# circuit_roboag.net
KiCad netlist of a schematic drawn in EAGLE
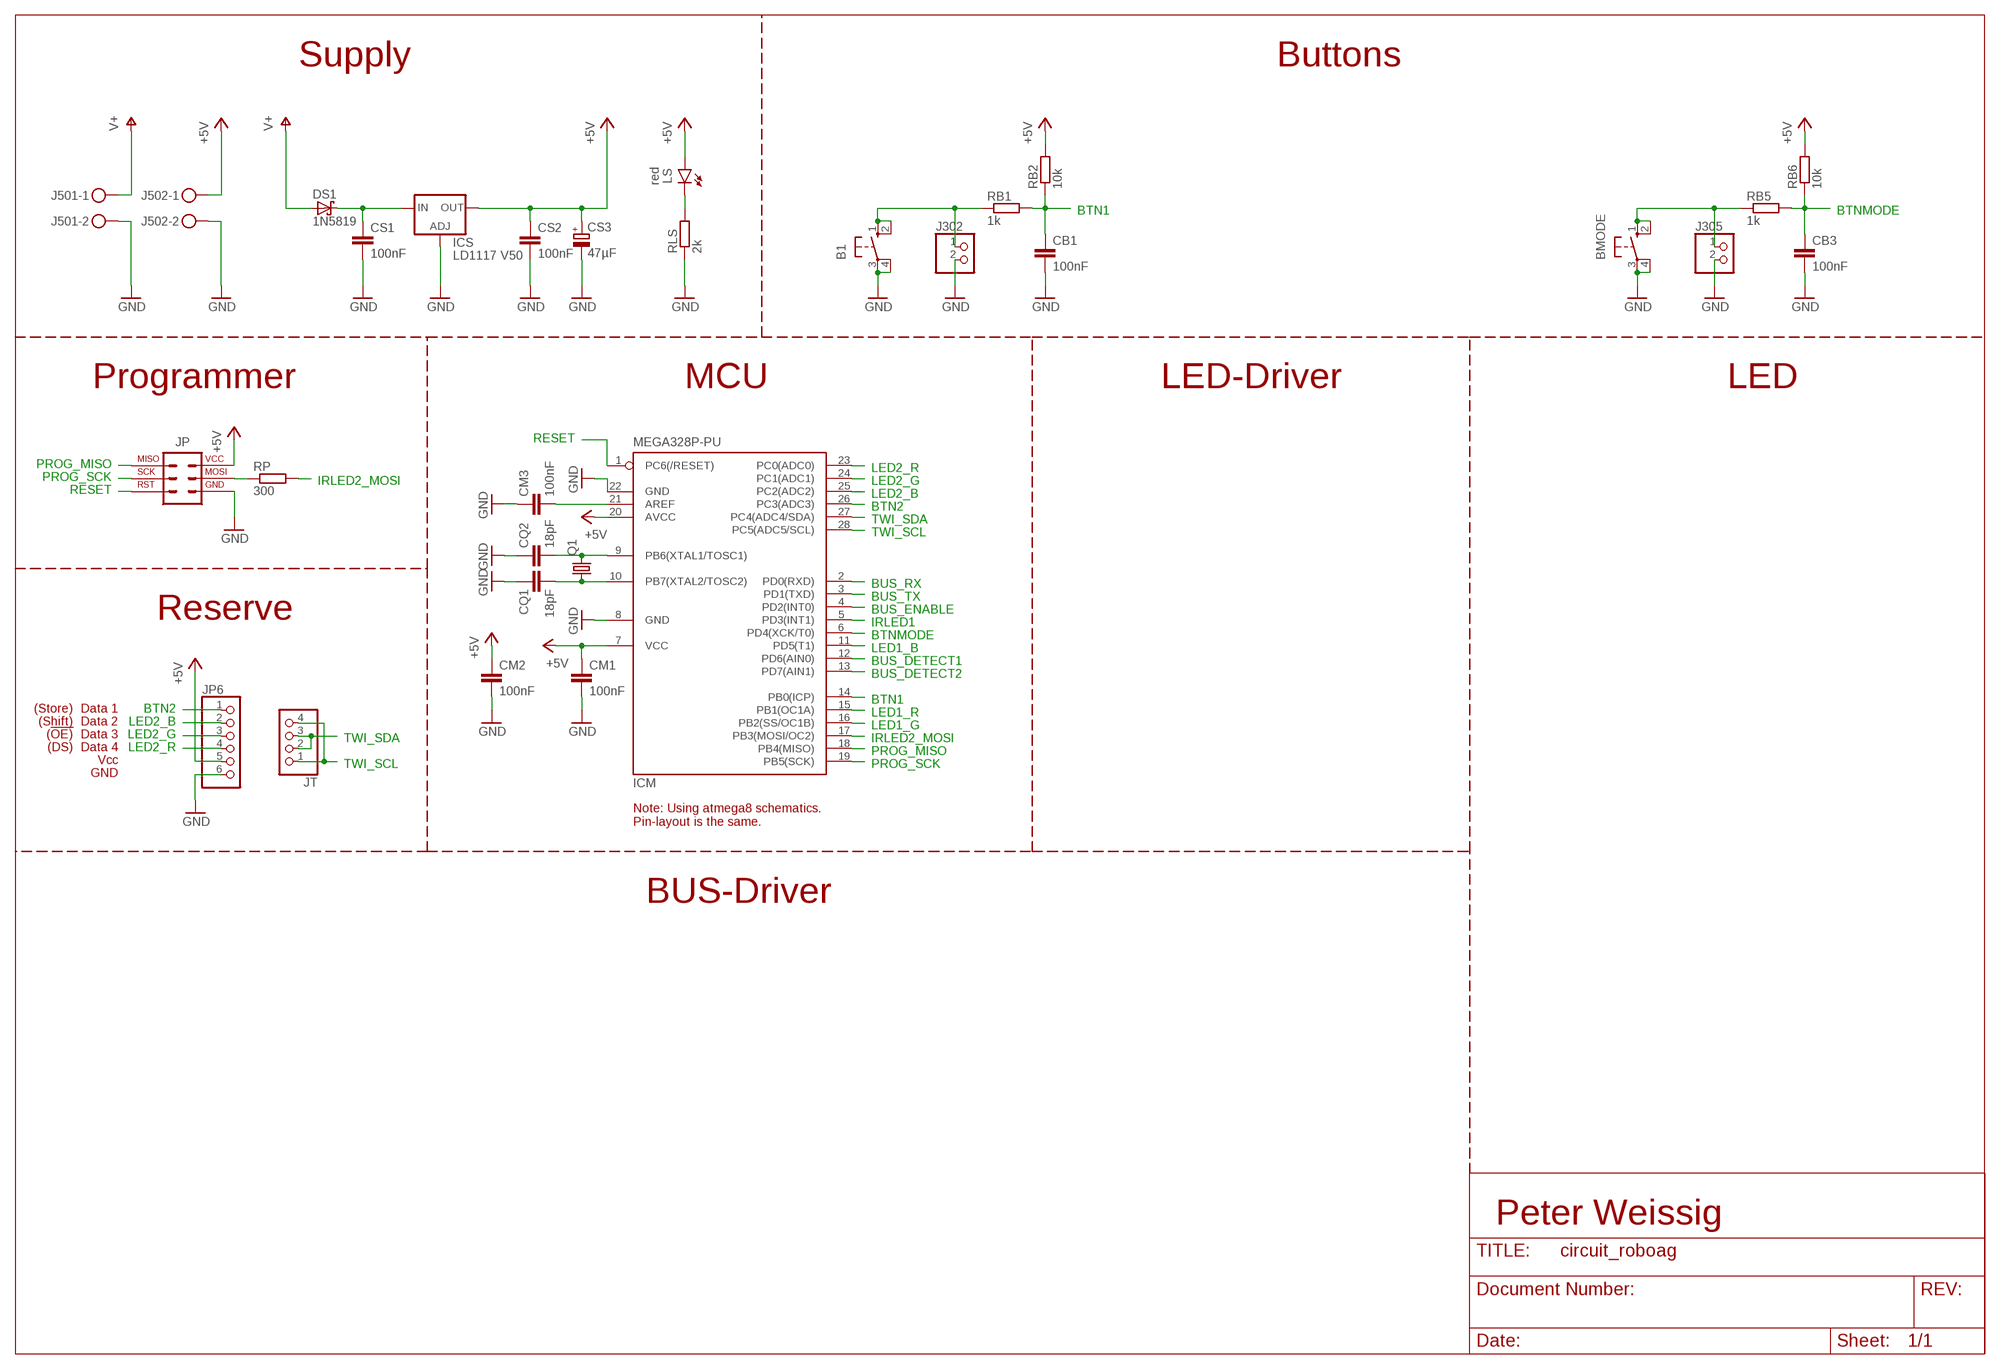
[diagram p0: schematic, sheet 1]

(export (version "E")
  (design (tool "Eeschema 10.0.6"))
  (components
    (comp (ref "B1")
      (value "10-XX")
      (footprint "eagle-import:B3F-10XX")
      (fields (field (name "MPN") "B3F-1000"))
      (libsource (lib "eagle-import") (part "10-XX"))
    )
    (comp (ref "BMODE")
      (value "10-XX")
      (footprint "eagle-import:B3F-10XX")
      (fields (field (name "MPN") "B3F-1000"))
      (libsource (lib "eagle-import") (part "10-XX"))
    )
    (comp (ref "CB1")
      (value "100nF")
      (footprint "eagle-import:C025-025X050")
      (libsource (lib "eagle-import") (part "C-EU025-025X050"))
    )
    (comp (ref "CB3")
      (value "100nF")
      (footprint "eagle-import:C025-025X050")
      (libsource (lib "eagle-import") (part "C-EU025-025X050"))
    )
    (comp (ref "CM1")
      (value "100nF")
      (footprint "eagle-import:C025-025X050")
      (libsource (lib "eagle-import") (part "C-EU025-025X050"))
    )
    (comp (ref "CM2")
      (value "100nF")
      (footprint "eagle-import:C025-025X050")
      (libsource (lib "eagle-import") (part "C-EU025-025X050"))
    )
    (comp (ref "CM3")
      (value "100nF")
      (footprint "eagle-import:C025-025X050")
      (libsource (lib "eagle-import") (part "C-EU025-025X050"))
    )
    (comp (ref "CQ1")
      (value "18pF")
      (footprint "eagle-import:C025-025X050")
      (libsource (lib "eagle-import") (part "C-EU025-025X050"))
    )
    (comp (ref "CQ2")
      (value "18pF")
      (footprint "eagle-import:C025-025X050")
      (libsource (lib "eagle-import") (part "C-EU025-025X050"))
    )
    (comp (ref "CS1")
      (value "100nF")
      (footprint "eagle-import:C025-025X050")
      (libsource (lib "eagle-import") (part "C-EU025-025X050"))
    )
    (comp (ref "CS2")
      (value "100nF")
      (footprint "eagle-import:C025-025X050")
      (libsource (lib "eagle-import") (part "C-EU025-025X050"))
    )
    (comp (ref "CS3")
      (value "47µF")
      (footprint "eagle-import:E2-5")
      (libsource (lib "eagle-import") (part "CPOL-EUE2-5"))
    )
    (comp (ref "DS1")
      (value "1N5819")
      (footprint "eagle-import:DO41-7.6")
      (libsource (lib "eagle-import") (part "1N5819-B"))
    )
    (comp (ref "ICM")
      (value "MEGA328P-PU")
      (footprint "eagle-import:DIL28-3")
      (libsource (lib "eagle-import") (part "MEGA8-P"))
    )
    (comp (ref "ICS")
      (value "LD1117 V50")
      (footprint "eagle-import:TO220L1")
      (libsource (lib "eagle-import") (part "LD117A?V50"))
    )
    (comp (ref "J302")
      (value "PINHD-1X2")
      (footprint "eagle-import:1X02")
      (libsource (lib "eagle-import") (part "PINHD-1X2"))
    )
    (comp (ref "J305")
      (value "PINHD-1X2")
      (footprint "eagle-import:1X02")
      (libsource (lib "eagle-import") (part "PINHD-1X2"))
    )
    (comp (ref "J501")
      (value "STECKER_SPG_2")
      (footprint "eagle-import:STECKER_SPG_2")
      (libsource (lib "eagle-import") (part "STECKER_SPG_2"))
    )
    (comp (ref "J502")
      (value "STECKER_SPG_2")
      (footprint "eagle-import:STECKER_SPG_2")
      (libsource (lib "eagle-import") (part "STECKER_SPG_2"))
    )
    (comp (ref "JP")
      (value "STECKER_ISP_6")
      (footprint "eagle-import:STECKER_WANNE_6")
      (libsource (lib "eagle-import") (part "STECKER_ISP_6"))
    )
    (comp (ref "JP6")
      (value "PINHD-1X6/90")
      (footprint "eagle-import:1X06_90")
      (libsource (lib "eagle-import") (part "PINHD-1X6/90"))
    )
    (comp (ref "JT")
      (value "PINHD-1X4")
      (footprint "eagle-import:1X04")
      (libsource (lib "eagle-import") (part "PINHD-1X4"))
    )
    (comp (ref "LS")
      (value "red")
      (footprint "eagle-import:LED_3MM")
      (libsource (lib "eagle-import") (part "LED-3MM"))
    )
    (comp (ref "Q1")
      (value "CRYSTALHC49U70")
      (footprint "eagle-import:HC49U70")
      (libsource (lib "eagle-import") (part "CRYSTALHC49U70"))
    )
    (comp (ref "RB1")
      (value "1k")
      (footprint "eagle-import:0207_10")
      (libsource (lib "eagle-import") (part "R-EU_0207/10"))
    )
    (comp (ref "RB2")
      (value "10k")
      (footprint "eagle-import:0207_10")
      (libsource (lib "eagle-import") (part "R-EU_0207/10"))
    )
    (comp (ref "RB5")
      (value "1k")
      (footprint "eagle-import:0207_10")
      (libsource (lib "eagle-import") (part "R-EU_0207/10"))
    )
    (comp (ref "RB6")
      (value "10k")
      (footprint "eagle-import:0207_10")
      (libsource (lib "eagle-import") (part "R-EU_0207/10"))
    )
    (comp (ref "RLS")
      (value "2k")
      (footprint "eagle-import:0207_10")
      (libsource (lib "eagle-import") (part "R-EU_0207/10"))
    )
    (comp (ref "RP")
      (value "300")
      (footprint "eagle-import:0207_10")
      (libsource (lib "eagle-import") (part "R-EU_0207/10"))
    )
  )
  (nets
    (net (code "1") (name "+5V") (class "Default")
      (node (ref "CM1") (pin "1") (pinfunction "1_1") (pintype "passive"))
      (node (ref "CM2") (pin "1") (pinfunction "1_1") (pintype "passive"))
      (node (ref "CS2") (pin "1") (pinfunction "1_1") (pintype "passive"))
      (node (ref "CS3") (pin "+") (pinfunction "+_+") (pintype "passive"))
      (node (ref "ICM") (pin "20") (pinfunction "AVCC_20") (pintype "power_in"))
      (node (ref "ICM") (pin "7") (pinfunction "VCC_7") (pintype "power_in"))
      (node (ref "ICS") (pin "2") (pinfunction "OUT_2") (pintype "passive"))
      (node (ref "J502") (pin "1") (pinfunction "KL_1") (pintype "passive"))
      (node (ref "JP") (pin "2") (pinfunction "2_VCC_2") (pintype "passive"))
      (node (ref "JP6") (pin "5") (pinfunction "5_5") (pintype "passive"))
      (node (ref "LS") (pin "A") (pinfunction "A_A") (pintype "passive"))
      (node (ref "RB2") (pin "2") (pinfunction "2_2") (pintype "passive"))
      (node (ref "RB6") (pin "2") (pinfunction "2_2") (pintype "passive"))
    )
    (net (code "2") (name "/BTN1") (class "Default")
      (node (ref "CB1") (pin "1") (pinfunction "1_1") (pintype "passive"))
      (node (ref "ICM") (pin "14") (pinfunction "PB0(ICP)_14") (pintype "bidirectional"))
      (node (ref "RB1") (pin "2") (pinfunction "2_2") (pintype "passive"))
      (node (ref "RB2") (pin "1") (pinfunction "1_1") (pintype "passive"))
    )
    (net (code "3") (name "/BTN2") (class "Default")
      (node (ref "ICM") (pin "26") (pinfunction "PC3(ADC3)_26") (pintype "bidirectional"))
      (node (ref "JP6") (pin "1") (pinfunction "1_1") (pintype "passive"))
    )
    (net (code "4") (name "/BTNMODE") (class "Default")
      (node (ref "CB3") (pin "1") (pinfunction "1_1") (pintype "passive"))
      (node (ref "ICM") (pin "6") (pinfunction "PD4(XCK/T0)_6") (pintype "bidirectional"))
      (node (ref "RB5") (pin "2") (pinfunction "2_2") (pintype "passive"))
      (node (ref "RB6") (pin "1") (pinfunction "1_1") (pintype "passive"))
    )
    (net (code "5") (name "/BUS_DETECT1") (class "Default")
      (node (ref "ICM") (pin "12") (pinfunction "PD6(AIN0)_12") (pintype "bidirectional"))
    )
    (net (code "6") (name "/BUS_DETECT2") (class "Default")
      (node (ref "ICM") (pin "13") (pinfunction "PD7(AIN1)_13") (pintype "bidirectional"))
    )
    (net (code "7") (name "/BUS_ENABLE") (class "Default")
      (node (ref "ICM") (pin "4") (pinfunction "PD2(INT0)_4") (pintype "bidirectional"))
    )
    (net (code "8") (name "/BUS_RX") (class "Default")
      (node (ref "ICM") (pin "2") (pinfunction "PD0(RXD)_2") (pintype "bidirectional"))
    )
    (net (code "9") (name "/BUS_TX") (class "Default")
      (node (ref "ICM") (pin "3") (pinfunction "PD1(TXD)_3") (pintype "bidirectional"))
    )
    (net (code "10") (name "/IRLED1") (class "Default")
      (node (ref "ICM") (pin "5") (pinfunction "PD3(INT1)_5") (pintype "bidirectional"))
    )
    (net (code "11") (name "/IRLED2_MOSI") (class "Default")
      (node (ref "ICM") (pin "17") (pinfunction "PB3(MOSI/OC2)_17") (pintype "bidirectional"))
      (node (ref "RP") (pin "2") (pinfunction "2_2") (pintype "passive"))
    )
    (net (code "12") (name "/LED1_B") (class "Default")
      (node (ref "ICM") (pin "11") (pinfunction "PD5(T1)_11") (pintype "bidirectional"))
    )
    (net (code "13") (name "/LED1_G") (class "Default")
      (node (ref "ICM") (pin "16") (pinfunction "PB2(SS/OC1B)_16") (pintype "bidirectional"))
    )
    (net (code "14") (name "/LED1_R") (class "Default")
      (node (ref "ICM") (pin "15") (pinfunction "PB1(OC1A)_15") (pintype "bidirectional"))
    )
    (net (code "15") (name "/LED2_B") (class "Default")
      (node (ref "ICM") (pin "25") (pinfunction "PC2(ADC2)_25") (pintype "bidirectional"))
      (node (ref "JP6") (pin "2") (pinfunction "2_2") (pintype "passive"))
    )
    (net (code "16") (name "/LED2_G") (class "Default")
      (node (ref "ICM") (pin "24") (pinfunction "PC1(ADC1)_24") (pintype "bidirectional"))
      (node (ref "JP6") (pin "3") (pinfunction "3_3") (pintype "passive"))
    )
    (net (code "17") (name "/LED2_R") (class "Default")
      (node (ref "ICM") (pin "23") (pinfunction "PC0(ADC0)_23") (pintype "bidirectional"))
      (node (ref "JP6") (pin "4") (pinfunction "4_4") (pintype "passive"))
    )
    (net (code "18") (name "/PROG_MISO") (class "Default")
      (node (ref "ICM") (pin "18") (pinfunction "PB4(MISO)_18") (pintype "bidirectional"))
      (node (ref "JP") (pin "1") (pinfunction "1_MISO_1") (pintype "passive"))
    )
    (net (code "19") (name "/PROG_SCK") (class "Default")
      (node (ref "ICM") (pin "19") (pinfunction "PB5(SCK)_19") (pintype "bidirectional"))
      (node (ref "JP") (pin "3") (pinfunction "3_SCK_3") (pintype "passive"))
    )
    (net (code "20") (name "/RESET") (class "Default")
      (node (ref "ICM") (pin "1") (pinfunction "PC6(/RESET)_1") (pintype "bidirectional"))
      (node (ref "JP") (pin "5") (pinfunction "5_RST_5") (pintype "passive"))
    )
    (net (code "21") (name "/TWI_SCL") (class "Default")
      (node (ref "ICM") (pin "28") (pinfunction "PC5(ADC5/SCL)_28") (pintype "bidirectional"))
      (node (ref "JT") (pin "1") (pinfunction "1_1") (pintype "passive"))
      (node (ref "JT") (pin "4") (pinfunction "4_4") (pintype "passive"))
    )
    (net (code "22") (name "/TWI_SDA") (class "Default")
      (node (ref "ICM") (pin "27") (pinfunction "PC4(ADC4/SDA)_27") (pintype "bidirectional"))
      (node (ref "JT") (pin "2") (pinfunction "2_2") (pintype "passive"))
      (node (ref "JT") (pin "3") (pinfunction "3_3") (pintype "passive"))
    )
    (net (code "23") (name "GND") (class "Default")
      (node (ref "B1") (pin "3") (pinfunction "P_3") (pintype "passive"))
      (node (ref "B1") (pin "4") (pinfunction "P1_4") (pintype "passive"))
      (node (ref "BMODE") (pin "3") (pinfunction "P_3") (pintype "passive"))
      (node (ref "BMODE") (pin "4") (pinfunction "P1_4") (pintype "passive"))
      (node (ref "CB1") (pin "2") (pinfunction "2_2") (pintype "passive"))
      (node (ref "CB3") (pin "2") (pinfunction "2_2") (pintype "passive"))
      (node (ref "CM1") (pin "2") (pinfunction "2_2") (pintype "passive"))
      (node (ref "CM2") (pin "2") (pinfunction "2_2") (pintype "passive"))
      (node (ref "CM3") (pin "1") (pinfunction "1_1") (pintype "passive"))
      (node (ref "CQ1") (pin "1") (pinfunction "1_1") (pintype "passive"))
      (node (ref "CQ2") (pin "1") (pinfunction "1_1") (pintype "passive"))
      (node (ref "CS1") (pin "2") (pinfunction "2_2") (pintype "passive"))
      (node (ref "CS2") (pin "2") (pinfunction "2_2") (pintype "passive"))
      (node (ref "CS3") (pin "-") (pinfunction "-_-") (pintype "passive"))
      (node (ref "ICM") (pin "22") (pinfunction "GND_22") (pintype "power_in"))
      (node (ref "ICM") (pin "8") (pinfunction "GND_8") (pintype "power_in"))
      (node (ref "ICS") (pin "1") (pinfunction "ADJ_1") (pintype "input"))
      (node (ref "J302") (pin "2") (pinfunction "2_2") (pintype "passive"))
      (node (ref "J305") (pin "2") (pinfunction "2_2") (pintype "passive"))
      (node (ref "J501") (pin "2") (pinfunction "KL_2") (pintype "passive"))
      (node (ref "J502") (pin "2") (pinfunction "KL_2") (pintype "passive"))
      (node (ref "JP") (pin "6") (pinfunction "6_GND_6") (pintype "passive"))
      (node (ref "JP6") (pin "6") (pinfunction "6_6") (pintype "passive"))
      (node (ref "RLS") (pin "1") (pinfunction "1_1") (pintype "passive"))
    )
    (net (code "24") (name "Net-(B1-S)") (class "Default")
      (node (ref "B1") (pin "1") (pinfunction "S_1") (pintype "passive"))
      (node (ref "B1") (pin "2") (pinfunction "S1_2") (pintype "passive"))
      (node (ref "J302") (pin "1") (pinfunction "1_1") (pintype "passive"))
      (node (ref "RB1") (pin "1") (pinfunction "1_1") (pintype "passive"))
    )
    (net (code "25") (name "Net-(BMODE-S)") (class "Default")
      (node (ref "BMODE") (pin "1") (pinfunction "S_1") (pintype "passive"))
      (node (ref "BMODE") (pin "2") (pinfunction "S1_2") (pintype "passive"))
      (node (ref "J305") (pin "1") (pinfunction "1_1") (pintype "passive"))
      (node (ref "RB5") (pin "1") (pinfunction "1_1") (pintype "passive"))
    )
    (net (code "26") (name "Net-(ICM-AREF)") (class "Default")
      (node (ref "CM3") (pin "2") (pinfunction "2_2") (pintype "passive"))
      (node (ref "ICM") (pin "21") (pinfunction "AREF_21") (pintype "passive"))
    )
    (net (code "27") (name "Net-(ICM-PB6(XTAL1{slash}TOSC1))") (class "Default")
      (node (ref "CQ2") (pin "2") (pinfunction "2_2") (pintype "passive"))
      (node (ref "ICM") (pin "9") (pinfunction "PB6(XTAL1/TOSC1)_9") (pintype "bidirectional"))
      (node (ref "Q1") (pin "2") (pinfunction "2_2") (pintype "passive"))
    )
    (net (code "28") (name "Net-(ICM-PB7(XTAL2{slash}TOSC2))") (class "Default")
      (node (ref "CQ1") (pin "2") (pinfunction "2_2") (pintype "passive"))
      (node (ref "ICM") (pin "10") (pinfunction "PB7(XTAL2/TOSC2)_10") (pintype "bidirectional"))
      (node (ref "Q1") (pin "1") (pinfunction "1_1") (pintype "passive"))
    )
    (net (code "29") (name "Net-(ICS-IN)") (class "Default")
      (node (ref "CS1") (pin "1") (pinfunction "1_1") (pintype "passive"))
      (node (ref "DS1") (pin "C") (pinfunction "C_C") (pintype "passive"))
      (node (ref "ICS") (pin "3") (pinfunction "IN_3") (pintype "input"))
    )
    (net (code "30") (name "Net-(JP-4_MOSI)") (class "Default")
      (node (ref "JP") (pin "4") (pinfunction "4_MOSI_4") (pintype "passive"))
      (node (ref "RP") (pin "1") (pinfunction "1_1") (pintype "passive"))
    )
    (net (code "31") (name "Net-(LS-C)") (class "Default")
      (node (ref "LS") (pin "K") (pinfunction "C_K") (pintype "passive"))
      (node (ref "RLS") (pin "2") (pinfunction "2_2") (pintype "passive"))
    )
    (net (code "32") (name "V+") (class "Default")
      (node (ref "DS1") (pin "A") (pinfunction "A_A") (pintype "passive"))
      (node (ref "J501") (pin "1") (pinfunction "KL_1") (pintype "passive"))
    )
  )
)
